# mc33926-connector-reva.net
KiCad netlist of a schematic drawn in EAGLE
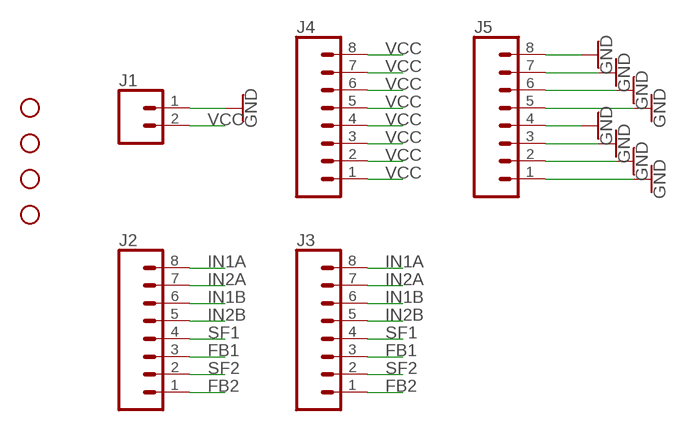
[diagram p0: schematic, sheet 1]

(export (version "E")
  (design (tool "Eeschema 10.0.6"))
  (components
    (comp (ref "H1")
      (value "STAND-OFF")
      (footprint "eagle-import:STAND-OFF")
      (libsource (lib "eagle-import") (part "STAND-OFF"))
    )
    (comp (ref "H2")
      (value "STAND-OFF")
      (footprint "eagle-import:STAND-OFF")
      (libsource (lib "eagle-import") (part "STAND-OFF"))
    )
    (comp (ref "H3")
      (value "STAND-OFF")
      (footprint "eagle-import:STAND-OFF")
      (libsource (lib "eagle-import") (part "STAND-OFF"))
    )
    (comp (ref "H4")
      (value "STAND-OFF")
      (footprint "eagle-import:STAND-OFF")
      (libsource (lib "eagle-import") (part "STAND-OFF"))
    )
    (comp (ref "J1")
      (value "CONN_02-JST-2MM-SMT")
      (footprint "eagle-import:JST-2-SMD")
      (libsource (lib "eagle-import") (part "CONN_02-JST-2MM-SMT"))
    )
    (comp (ref "J2")
      (value "CONN_08\"")
      (footprint "eagle-import:1X08")
      (libsource (lib "eagle-import") (part "CONN_08{dblquote}"))
    )
    (comp (ref "J3")
      (value "CONN_08\"")
      (footprint "eagle-import:1X08")
      (libsource (lib "eagle-import") (part "CONN_08{dblquote}"))
    )
    (comp (ref "J4")
      (value "CONN_08\"")
      (footprint "eagle-import:1X08")
      (libsource (lib "eagle-import") (part "CONN_08{dblquote}"))
    )
    (comp (ref "J5")
      (value "CONN_08\"")
      (footprint "eagle-import:1X08")
      (libsource (lib "eagle-import") (part "CONN_08{dblquote}"))
    )
  )
  (nets
    (net (code "1") (name "/FB1") (class "Default")
      (node (ref "J2") (pin "3") (pinfunction "3_3") (pintype "passive"))
      (node (ref "J3") (pin "3") (pinfunction "3_3") (pintype "passive"))
    )
    (net (code "2") (name "/FB2") (class "Default")
      (node (ref "J2") (pin "1") (pinfunction "1_1") (pintype "passive"))
      (node (ref "J3") (pin "1") (pinfunction "1_1") (pintype "passive"))
    )
    (net (code "3") (name "/IN1A") (class "Default")
      (node (ref "J2") (pin "8") (pinfunction "8_8") (pintype "passive"))
      (node (ref "J3") (pin "8") (pinfunction "8_8") (pintype "passive"))
    )
    (net (code "4") (name "/IN1B") (class "Default")
      (node (ref "J2") (pin "6") (pinfunction "6_6") (pintype "passive"))
      (node (ref "J3") (pin "6") (pinfunction "6_6") (pintype "passive"))
    )
    (net (code "5") (name "/IN2A") (class "Default")
      (node (ref "J2") (pin "7") (pinfunction "7_7") (pintype "passive"))
      (node (ref "J3") (pin "7") (pinfunction "7_7") (pintype "passive"))
    )
    (net (code "6") (name "/IN2B") (class "Default")
      (node (ref "J2") (pin "5") (pinfunction "5_5") (pintype "passive"))
      (node (ref "J3") (pin "5") (pinfunction "5_5") (pintype "passive"))
    )
    (net (code "7") (name "/SF1") (class "Default")
      (node (ref "J2") (pin "4") (pinfunction "4_4") (pintype "passive"))
      (node (ref "J3") (pin "4") (pinfunction "4_4") (pintype "passive"))
    )
    (net (code "8") (name "/SF2") (class "Default")
      (node (ref "J2") (pin "2") (pinfunction "2_2") (pintype "passive"))
      (node (ref "J3") (pin "2") (pinfunction "2_2") (pintype "passive"))
    )
    (net (code "9") (name "/VCC") (class "Default")
      (node (ref "J1") (pin "2") (pinfunction "1_2") (pintype "passive"))
      (node (ref "J4") (pin "1") (pinfunction "1_1") (pintype "passive"))
      (node (ref "J4") (pin "2") (pinfunction "2_2") (pintype "passive"))
      (node (ref "J4") (pin "3") (pinfunction "3_3") (pintype "passive"))
      (node (ref "J4") (pin "4") (pinfunction "4_4") (pintype "passive"))
      (node (ref "J4") (pin "5") (pinfunction "5_5") (pintype "passive"))
      (node (ref "J4") (pin "6") (pinfunction "6_6") (pintype "passive"))
      (node (ref "J4") (pin "7") (pinfunction "7_7") (pintype "passive"))
      (node (ref "J4") (pin "8") (pinfunction "8_8") (pintype "passive"))
    )
    (net (code "10") (name "GND") (class "Default")
      (node (ref "J1") (pin "1") (pinfunction "2_1") (pintype "passive"))
      (node (ref "J5") (pin "1") (pinfunction "1_1") (pintype "passive"))
      (node (ref "J5") (pin "2") (pinfunction "2_2") (pintype "passive"))
      (node (ref "J5") (pin "3") (pinfunction "3_3") (pintype "passive"))
      (node (ref "J5") (pin "4") (pinfunction "4_4") (pintype "passive"))
      (node (ref "J5") (pin "5") (pinfunction "5_5") (pintype "passive"))
      (node (ref "J5") (pin "6") (pinfunction "6_6") (pintype "passive"))
      (node (ref "J5") (pin "7") (pinfunction "7_7") (pintype "passive"))
      (node (ref "J5") (pin "8") (pinfunction "8_8") (pintype "passive"))
    )
  )
)
